# ESP-03_to_AVR_ISP.net
KiCad netlist of a schematic drawn in EAGLE
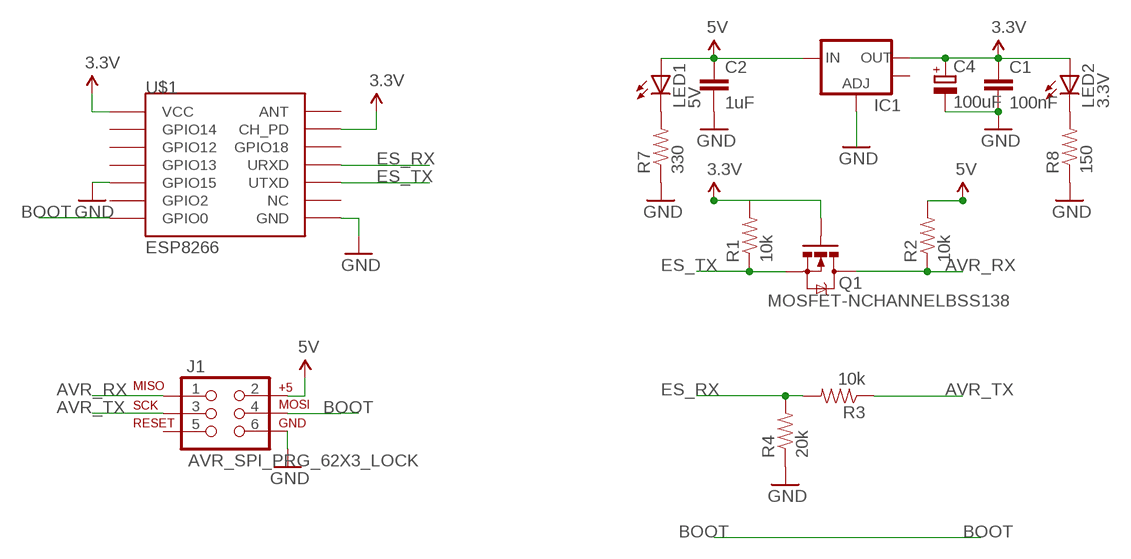
[diagram p0: schematic, sheet 1]

(export (version "E")
  (design (tool "Eeschema 10.0.6"))
  (components
    (comp (ref "C1")
      (value "100nF")
      (footprint "eagle-import:0603-CAP")
      (libsource (lib "eagle-import") (part "CAP0603-CAP"))
    )
    (comp (ref "C2")
      (value "1uF")
      (footprint "eagle-import:0603-CAP")
      (libsource (lib "eagle-import") (part "CAP0603-CAP"))
    )
    (comp (ref "C4")
      (value "100uF")
      (footprint "eagle-import:B_3528-21R")
      (libsource (lib "eagle-import") (part "CPOL-EUB/3528-21R"))
    )
    (comp (ref "IC1")
      (value "V_REG_LM1117SOT223")
      (footprint "eagle-import:SOT223")
      (libsource (lib "eagle-import") (part "V_REG_LM1117SOT223"))
    )
    (comp (ref "J1")
      (value "AVR_SPI_PRG_62X3_LOCK")
      (footprint "eagle-import:2X3_LOCK")
      (libsource (lib "eagle-import") (part "AVR_SPI_PRG_62X3_LOCK"))
    )
    (comp (ref "LED1")
      (value "5V")
      (footprint "eagle-import:LED-0603")
      (libsource (lib "eagle-import") (part "LED0603"))
    )
    (comp (ref "LED2")
      (value "3.3V")
      (footprint "eagle-import:LED-0603")
      (libsource (lib "eagle-import") (part "LED0603"))
    )
    (comp (ref "Q1")
      (value "MOSFET-NCHANNELBSS138")
      (footprint "eagle-import:SOT23-3")
      (libsource (lib "eagle-import") (part "MOSFET-NCHANNELBSS138"))
    )
    (comp (ref "R1")
      (value "10k")
      (footprint "eagle-import:0603-RES")
      (libsource (lib "eagle-import") (part "RESISTOR0603-RES"))
    )
    (comp (ref "R2")
      (value "10k")
      (footprint "eagle-import:0603-RES")
      (libsource (lib "eagle-import") (part "RESISTOR0603-RES"))
    )
    (comp (ref "R3")
      (value "10k")
      (footprint "eagle-import:0603-RES")
      (libsource (lib "eagle-import") (part "RESISTOR0603-RES"))
    )
    (comp (ref "R4")
      (value "20k")
      (footprint "eagle-import:0603-RES")
      (libsource (lib "eagle-import") (part "RESISTOR0603-RES"))
    )
    (comp (ref "R7")
      (value "330")
      (footprint "eagle-import:0603-RES")
      (libsource (lib "eagle-import") (part "RESISTOR0603"))
    )
    (comp (ref "R8")
      (value "150")
      (footprint "eagle-import:0603-RES")
      (libsource (lib "eagle-import") (part "RESISTOR0603"))
    )
    (comp (ref "U$1")
      (value "ESP8266")
      (footprint "eagle-import:ESP-03")
      (libsource (lib "eagle-import") (part "ESP8266"))
    )
  )
  (nets
    (net (code "1") (name "/AVR_RX") (class "Default")
      (node (ref "J1") (pin "1") (pinfunction "1_1") (pintype "passive"))
      (node (ref "Q1") (pin "3") (pinfunction "D_3") (pintype "passive"))
      (node (ref "R2") (pin "1") (pinfunction "1_1") (pintype "passive"))
    )
    (net (code "2") (name "/AVR_TX") (class "Default")
      (node (ref "J1") (pin "3") (pinfunction "3_3") (pintype "passive"))
      (node (ref "R3") (pin "1") (pinfunction "1_1") (pintype "passive"))
    )
    (net (code "3") (name "/BOOT") (class "Default")
      (node (ref "J1") (pin "4") (pinfunction "4_4") (pintype "passive"))
      (node (ref "U$1") (pin "GPIO0") (pinfunction "GPIO0_GPIO0") (pintype "bidirectional"))
    )
    (net (code "4") (name "/ES_RX") (class "Default")
      (node (ref "R3") (pin "2") (pinfunction "2_2") (pintype "passive"))
      (node (ref "R4") (pin "2") (pinfunction "2_2") (pintype "passive"))
      (node (ref "U$1") (pin "URXD") (pinfunction "URXD_URXD") (pintype "bidirectional"))
    )
    (net (code "5") (name "/ES_TX") (class "Default")
      (node (ref "Q1") (pin "2") (pinfunction "S_2") (pintype "passive"))
      (node (ref "R1") (pin "1") (pinfunction "1_1") (pintype "passive"))
      (node (ref "U$1") (pin "UTXD") (pinfunction "UTXD_UTXD") (pintype "bidirectional"))
    )
    (net (code "6") (name "3.3V") (class "Default")
      (node (ref "C1") (pin "1") (pinfunction "1_1") (pintype "passive"))
      (node (ref "C4") (pin "+") (pinfunction "+_+") (pintype "passive"))
      (node (ref "IC1") (pin "2") (pinfunction "OUT_2") (pintype "output"))
      (node (ref "LED2") (pin "A") (pinfunction "A_A") (pintype "passive"))
      (node (ref "Q1") (pin "1") (pinfunction "G_1") (pintype "passive"))
      (node (ref "R1") (pin "2") (pinfunction "2_2") (pintype "passive"))
      (node (ref "U$1") (pin "CH_PD") (pinfunction "CH_PD_CH_PD") (pintype "bidirectional"))
      (node (ref "U$1") (pin "VCC") (pinfunction "VCC_VCC") (pintype "bidirectional"))
    )
    (net (code "7") (name "5V") (class "Default")
      (node (ref "C2") (pin "1") (pinfunction "1_1") (pintype "passive"))
      (node (ref "IC1") (pin "3") (pinfunction "IN_3") (pintype "input"))
      (node (ref "J1") (pin "2") (pinfunction "2_2") (pintype "passive"))
      (node (ref "LED1") (pin "A") (pinfunction "A_A") (pintype "passive"))
      (node (ref "R2") (pin "2") (pinfunction "2_2") (pintype "passive"))
    )
    (net (code "8") (name "GND") (class "Default")
      (node (ref "C1") (pin "2") (pinfunction "2_2") (pintype "passive"))
      (node (ref "C2") (pin "2") (pinfunction "2_2") (pintype "passive"))
      (node (ref "C4") (pin "-") (pinfunction "-_-") (pintype "passive"))
      (node (ref "IC1") (pin "1") (pinfunction "ADJ_1") (pintype "input"))
      (node (ref "J1") (pin "6") (pinfunction "6_6") (pintype "passive"))
      (node (ref "R4") (pin "1") (pinfunction "1_1") (pintype "passive"))
      (node (ref "R7") (pin "1") (pinfunction "1_1") (pintype "passive"))
      (node (ref "R8") (pin "1") (pinfunction "1_1") (pintype "passive"))
      (node (ref "U$1") (pin "GND") (pinfunction "GND_GND") (pintype "bidirectional"))
      (node (ref "U$1") (pin "GPIO15") (pinfunction "GPIO15_GPIO15") (pintype "bidirectional"))
    )
    (net (code "9") (name "Net-(LED1-PadC)") (class "Default")
      (node (ref "LED1") (pin "C") (pinfunction "C_C") (pintype "passive"))
      (node (ref "R7") (pin "2") (pinfunction "2_2") (pintype "passive"))
    )
    (net (code "10") (name "Net-(LED2-PadC)") (class "Default")
      (node (ref "LED2") (pin "C") (pinfunction "C_C") (pintype "passive"))
      (node (ref "R8") (pin "2") (pinfunction "2_2") (pintype "passive"))
    )
    (net (code "11") (name "unconnected-(IC1-OUT-Pad4)") (class "Default")
      (node (ref "IC1") (pin "4") (pinfunction "OUT_4") (pintype "output"))
    )
    (net (code "12") (name "unconnected-(J1-Pad5)") (class "Default")
      (node (ref "J1") (pin "5") (pinfunction "5_5") (pintype "passive"))
    )
    (net (code "13") (name "unconnected-(U$1-PadANT)") (class "Default")
      (node (ref "U$1") (pin "ANT") (pinfunction "ANT_ANT") (pintype "bidirectional"))
    )
    (net (code "14") (name "unconnected-(U$1-PadGPIO2)") (class "Default")
      (node (ref "U$1") (pin "GPIO2") (pinfunction "GPIO2_GPIO2") (pintype "bidirectional"))
    )
    (net (code "15") (name "unconnected-(U$1-PadGPIO12)") (class "Default")
      (node (ref "U$1") (pin "GPIO12") (pinfunction "GPIO12_GPIO12") (pintype "bidirectional"))
    )
    (net (code "16") (name "unconnected-(U$1-PadGPIO13)") (class "Default")
      (node (ref "U$1") (pin "GPIO13") (pinfunction "GPIO13_GPIO13") (pintype "bidirectional"))
    )
    (net (code "17") (name "unconnected-(U$1-PadGPIO14)") (class "Default")
      (node (ref "U$1") (pin "GPIO14") (pinfunction "GPIO14_GPIO14") (pintype "bidirectional"))
    )
    (net (code "18") (name "unconnected-(U$1-PadGPIO18)") (class "Default")
      (node (ref "U$1") (pin "GPIO18") (pinfunction "GPIO18_GPIO18") (pintype "bidirectional"))
    )
    (net (code "19") (name "unconnected-(U$1-PadNC)") (class "Default")
      (node (ref "U$1") (pin "NC") (pinfunction "NC_NC") (pintype "bidirectional"))
    )
  )
)
